# design.net
KiCad netlist of a schematic drawn in Altium Designer
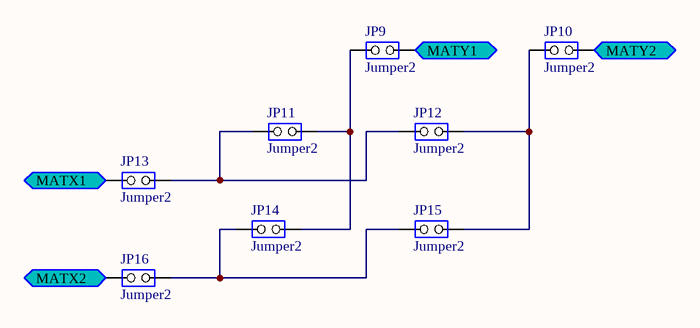
[diagram p0: 开关矩阵.SchDoc]

(export (version "E")
  (design (tool "Eeschema 10.0.6"))
  (components
    (comp (ref "JP9")
      (value "Jumper2")
      (footprint "CON2-P2.54")
      (libsource (lib "Miscellaneous Connectors") (part "Jumper2"))
    )
    (comp (ref "JP10")
      (value "Jumper2")
      (footprint "CON2-P2.54")
      (libsource (lib "Miscellaneous Connectors") (part "Jumper2"))
    )
    (comp (ref "JP11")
      (value "Jumper2")
      (footprint "CON2-P2.54")
      (libsource (lib "Miscellaneous Connectors") (part "Jumper2"))
    )
    (comp (ref "JP12")
      (value "Jumper2")
      (footprint "CON2-P2.54")
      (libsource (lib "Miscellaneous Connectors") (part "Jumper2"))
    )
    (comp (ref "JP13")
      (value "Jumper2")
      (footprint "CON2-P2.54")
      (libsource (lib "Miscellaneous Connectors") (part "Jumper2"))
    )
    (comp (ref "JP14")
      (value "Jumper2")
      (footprint "CON2-P2.54")
      (libsource (lib "Miscellaneous Connectors") (part "Jumper2"))
    )
    (comp (ref "JP15")
      (value "Jumper2")
      (footprint "CON2-P2.54")
      (libsource (lib "Miscellaneous Connectors") (part "Jumper2"))
    )
    (comp (ref "JP16")
      (value "Jumper2")
      (footprint "CON2-P2.54")
      (libsource (lib "Miscellaneous Connectors") (part "Jumper2"))
    )
  )
  (nets
    (net (code "1") (name "/MATX1") (class "Default")
      (node (ref "JP13") (pin "1") (pinfunction "COMMON_1") (pintype "passive"))
    )
    (net (code "2") (name "/MATX2") (class "Default")
      (node (ref "JP16") (pin "1") (pinfunction "COMMON_1") (pintype "passive"))
    )
    (net (code "3") (name "/MATY1") (class "Default")
      (node (ref "JP9") (pin "2") (pinfunction "NO_2") (pintype "passive"))
    )
    (net (code "4") (name "/MATY2") (class "Default")
      (node (ref "JP10") (pin "2") (pinfunction "NO_2") (pintype "passive"))
    )
    (net (code "5") (name "Net-(JP10-COMMON)") (class "Default")
      (node (ref "JP10") (pin "1") (pinfunction "COMMON_1") (pintype "passive"))
      (node (ref "JP12") (pin "2") (pinfunction "NO_2") (pintype "passive"))
      (node (ref "JP15") (pin "2") (pinfunction "NO_2") (pintype "passive"))
    )
    (net (code "6") (name "Net-(JP11-COMMON)") (class "Default")
      (node (ref "JP11") (pin "1") (pinfunction "COMMON_1") (pintype "passive"))
      (node (ref "JP12") (pin "1") (pinfunction "COMMON_1") (pintype "passive"))
      (node (ref "JP13") (pin "2") (pinfunction "NO_2") (pintype "passive"))
    )
    (net (code "7") (name "Net-(JP11-NO)") (class "Default")
      (node (ref "JP11") (pin "2") (pinfunction "NO_2") (pintype "passive"))
      (node (ref "JP14") (pin "2") (pinfunction "NO_2") (pintype "passive"))
      (node (ref "JP9") (pin "1") (pinfunction "COMMON_1") (pintype "passive"))
    )
    (net (code "8") (name "Net-(JP14-COMMON)") (class "Default")
      (node (ref "JP14") (pin "1") (pinfunction "COMMON_1") (pintype "passive"))
      (node (ref "JP15") (pin "1") (pinfunction "COMMON_1") (pintype "passive"))
      (node (ref "JP16") (pin "2") (pinfunction "NO_2") (pintype "passive"))
    )
  )
)
